# Simple-Fet_-v016-pro-mini.net
KiCad netlist of a schematic drawn in EAGLE
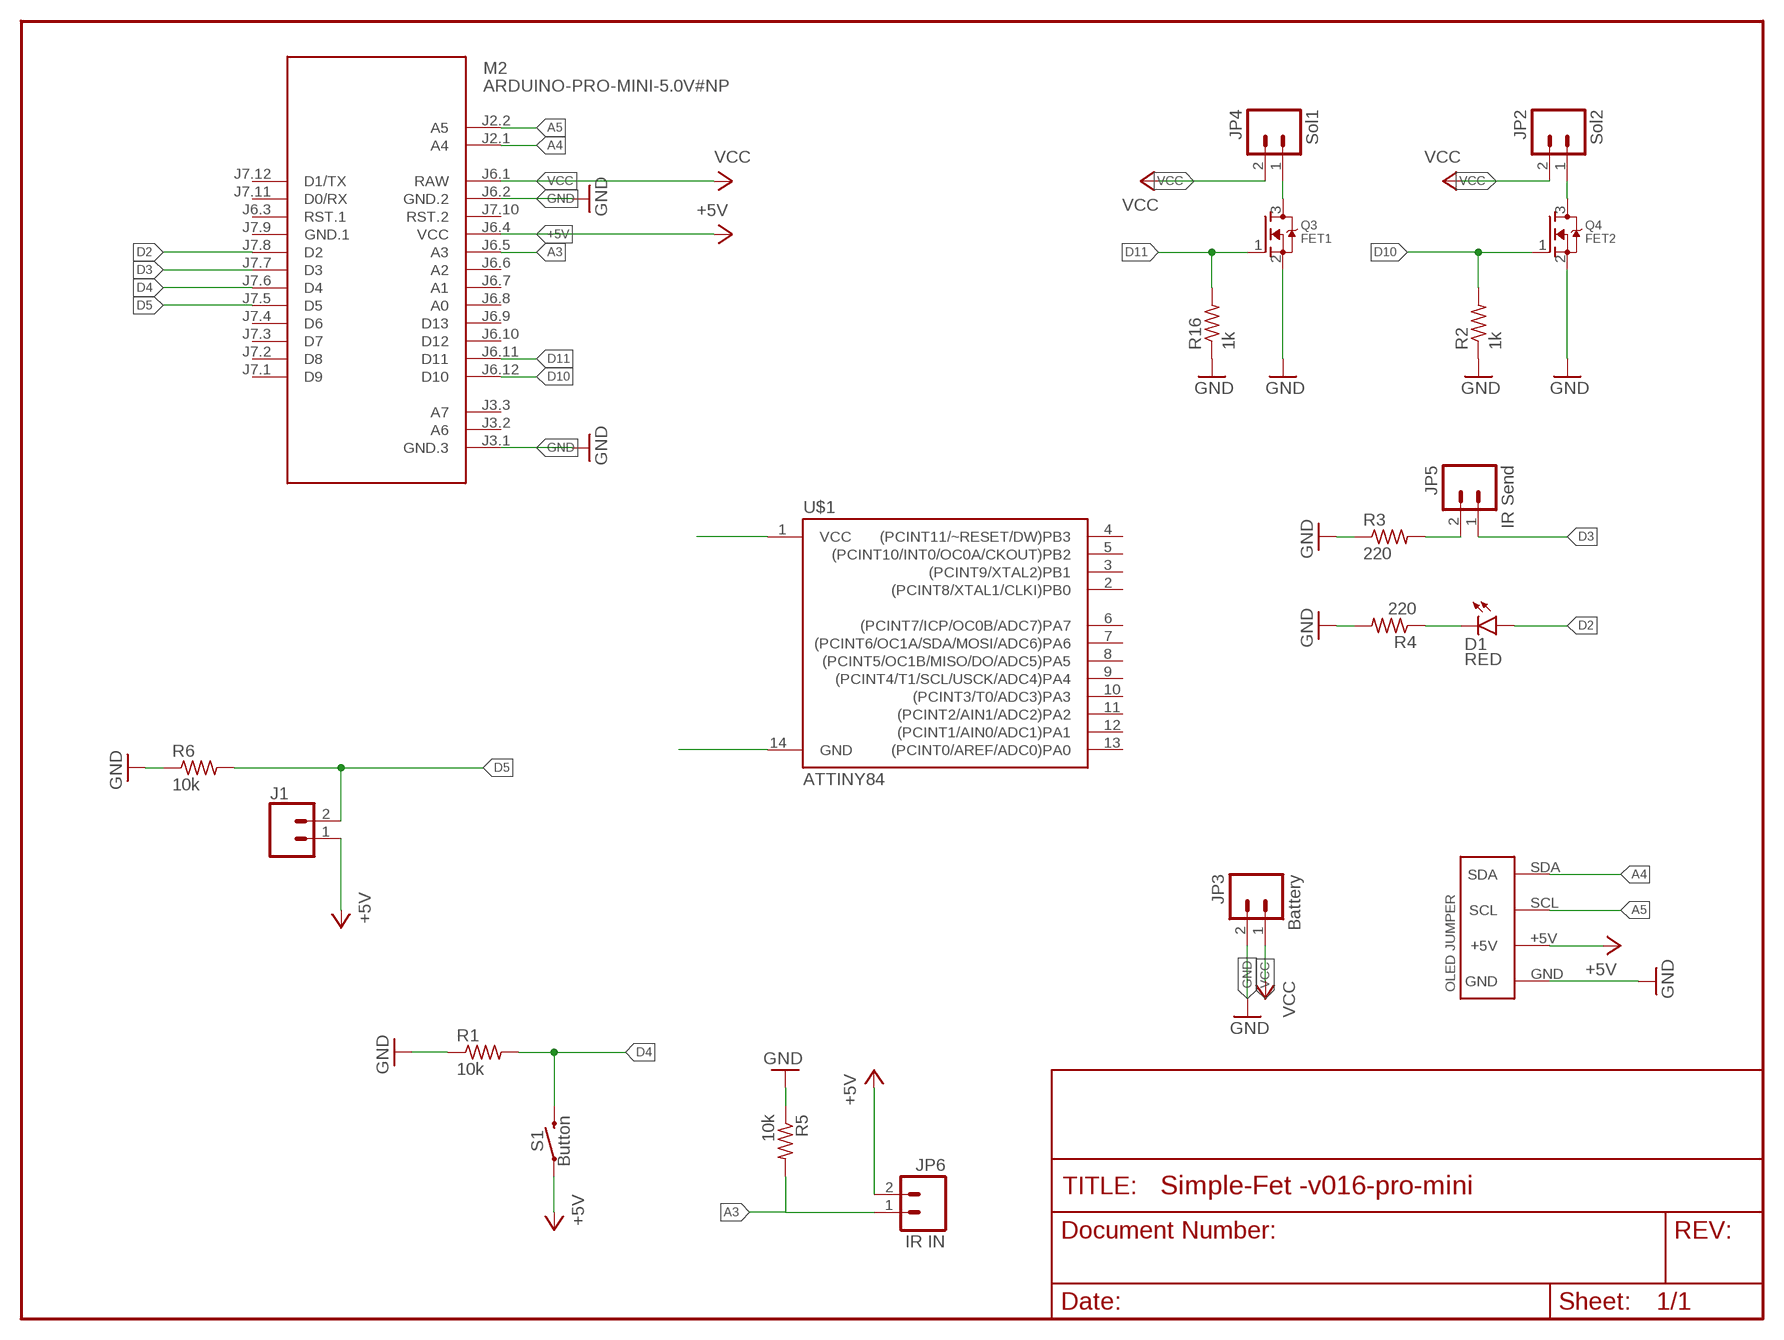
[diagram p0: schematic, sheet 1]

(export (version "E")
  (design (tool "Eeschema 10.0.6"))
  (components
    (comp (ref "D1")
      (value "RED")
      (footprint "eagle-import:LED-1206")
      (fields (field (name "MPN") "HSMC-C150"))
      (libsource (lib "eagle-import") (part "LED-RED1206"))
    )
    (comp (ref "J1")
      (value "CONN_02POGO_PIN_HOLES_ONLY")
      (footprint "eagle-import:1X02_PP_HOLES_ONLY")
      (libsource (lib "eagle-import") (part "CONN_02POGO_PIN_HOLES_ONLY"))
    )
    (comp (ref "JP2")
      (value "Sol2")
      (footprint "eagle-import:1X02")
      (fields (field (name "MF") "MOLEX") (field (name "MPN") "22-23-2021"))
      (libsource (lib "eagle-import") (part "M02PTH"))
    )
    (comp (ref "JP3")
      (value "Battery")
      (footprint "eagle-import:1X02")
      (fields (field (name "MF") "KEYSTONE ELECTR") (field (name "MPN") "2239"))
      (libsource (lib "eagle-import") (part "M02PTH"))
    )
    (comp (ref "JP4")
      (value "Sol1")
      (footprint "eagle-import:1X02")
      (fields (field (name "MF") "MOLEX") (field (name "MPN") "22-23-2021"))
      (libsource (lib "eagle-import") (part "M02PTH"))
    )
    (comp (ref "JP5")
      (value "IR Send")
      (footprint "eagle-import:1X02")
      (fields (field (name "MF") "FAIRCHILD SEMICONDUCTOR") (field (name "MPN") "QEE122"))
      (libsource (lib "eagle-import") (part "M02PTH"))
    )
    (comp (ref "JP6")
      (value "IR IN")
      (footprint "eagle-import:1X02")
      (fields (field (name "MF") "FAIRCHILD SEMICONDUCTOR") (field (name "MPN") "QEE113"))
      (libsource (lib "eagle-import") (part "M02PTH"))
    )
    (comp (ref "M2")
      (value "ARDUINO-PRO-MINI-5.0V#NP")
      (footprint "eagle-import:ARDUINO-PRO-MINI#NP")
      (libsource (lib "eagle-import") (part "ARDUINO-PRO-MINI-#NP5.0V"))
    )
    (comp (ref "Q3")
      (value "FET1")
      (footprint "eagle-import:SOT23")
      (fields (field (name "MPN") "SI2392ADS-T1-GE3"))
      (libsource (lib "eagle-import") (part "MOSFET-NREFLOW"))
    )
    (comp (ref "Q4")
      (value "FET2")
      (footprint "eagle-import:SOT23")
      (fields (field (name "MPN") "SI2392ADS-T1-GE3"))
      (libsource (lib "eagle-import") (part "MOSFET-NREFLOW"))
    )
    (comp (ref "R1")
      (value "10k")
      (footprint "eagle-import:M1206")
      (fields (field (name "MPN") "MC1206S4F1002T5E"))
      (libsource (lib "eagle-import") (part "R-US_M1206"))
    )
    (comp (ref "R2")
      (value "1k")
      (footprint "eagle-import:M1206")
      (fields (field (name "MPN") "RT1206FRE071KL"))
      (libsource (lib "eagle-import") (part "R-US_M1206"))
    )
    (comp (ref "R3")
      (value "220")
      (footprint "eagle-import:M1206")
      (fields (field (name "MF") "BOURNS, INC.") (field (name "MPN") "CR1206FX2200ELF"))
      (libsource (lib "eagle-import") (part "R-US_M1206"))
    )
    (comp (ref "R4")
      (value "220")
      (footprint "eagle-import:M1206")
      (fields (field (name "MF") "BOURNS, INC.") (field (name "MPN") "CR1206FX2200ELF"))
      (libsource (lib "eagle-import") (part "R-US_M1206"))
    )
    (comp (ref "R5")
      (value "10k")
      (footprint "eagle-import:M1206")
      (fields (field (name "MPN") "MC1206S4F1002T5E"))
      (libsource (lib "eagle-import") (part "R-US_M1206"))
    )
    (comp (ref "R6")
      (value "10k")
      (footprint "eagle-import:M1206")
      (fields (field (name "MPN") "MC1206S4F1002T5E"))
      (libsource (lib "eagle-import") (part "R-US_M1206"))
    )
    (comp (ref "R16")
      (value "1k")
      (footprint "eagle-import:M1206")
      (fields (field (name "MPN") "RT1206FRE071KL"))
      (libsource (lib "eagle-import") (part "R-US_M1206"))
    )
    (comp (ref "S1")
      (value "Button")
      (footprint "eagle-import:TACTILE_SWITCH_SMD_6.0X3.5MM")
      (libsource (lib "eagle-import") (part "MOMENTARY-SWITCH-SPST-SMD-6.0X3.5MM"))
    )
    (comp (ref "U$1")
      (value "ATTINY84")
      (footprint "eagle-import:SO14")
      (libsource (lib "eagle-import") (part "ATTINY84"))
    )
    (comp (ref "U$2")
      (value "OLEDHEADER")
      (footprint "eagle-import:OLED-CON")
      (libsource (lib "eagle-import") (part "OLEDHEADER"))
    )
  )
  (nets
    (net (code "1") (name "+5V") (class "Default")
      (node (ref "J1") (pin "1") (pinfunction "1_1") (pintype "passive"))
      (node (ref "JP6") (pin "2") (pinfunction "2_2") (pintype "passive"))
      (node (ref "M2") (pin "J6.4") (pinfunction "VCC_J6.4") (pintype "power_in"))
      (node (ref "S1") (pin "1") (pinfunction "1_1") (pintype "passive"))
      (node (ref "U$2") (pin "+5V") (pinfunction "+5V_+5V") (pintype "bidirectional"))
    )
    (net (code "2") (name "/GND.1") (class "Default")
      (node (ref "M2") (pin "J7.9") (pinfunction "GND.1_J7.9") (pintype "power_in"))
    )
    (net (code "3") (name "A3") (class "Default")
      (node (ref "JP6") (pin "1") (pinfunction "1_1") (pintype "passive"))
      (node (ref "M2") (pin "J6.5") (pinfunction "A3_J6.5") (pintype "bidirectional"))
      (node (ref "R5") (pin "2") (pinfunction "2_2") (pintype "passive"))
    )
    (net (code "4") (name "A4") (class "Default")
      (node (ref "M2") (pin "J2.1") (pinfunction "A4_J2.1") (pintype "bidirectional"))
      (node (ref "U$2") (pin "SDA") (pinfunction "SDA_SDA") (pintype "bidirectional"))
    )
    (net (code "5") (name "A5") (class "Default")
      (node (ref "M2") (pin "J2.2") (pinfunction "A5_J2.2") (pintype "bidirectional"))
      (node (ref "U$2") (pin "SCL") (pinfunction "SCL_SCL") (pintype "bidirectional"))
    )
    (net (code "6") (name "D2") (class "Default")
      (node (ref "D1") (pin "A") (pinfunction "A_A") (pintype "passive"))
      (node (ref "M2") (pin "J7.8") (pinfunction "D2_J7.8") (pintype "bidirectional"))
    )
    (net (code "7") (name "D3") (class "Default")
      (node (ref "JP5") (pin "1") (pinfunction "1_1") (pintype "passive"))
      (node (ref "M2") (pin "J7.7") (pinfunction "D3_J7.7") (pintype "bidirectional"))
    )
    (net (code "8") (name "D4") (class "Default")
      (node (ref "M2") (pin "J7.6") (pinfunction "D4_J7.6") (pintype "bidirectional"))
      (node (ref "R1") (pin "2") (pinfunction "2_2") (pintype "passive"))
      (node (ref "S1") (pin "2") (pinfunction "2_2") (pintype "passive"))
    )
    (net (code "9") (name "D5") (class "Default")
      (node (ref "J1") (pin "2") (pinfunction "2_2") (pintype "passive"))
      (node (ref "M2") (pin "J7.5") (pinfunction "D5_J7.5") (pintype "bidirectional"))
      (node (ref "R6") (pin "2") (pinfunction "2_2") (pintype "passive"))
    )
    (net (code "10") (name "D10") (class "Default")
      (node (ref "M2") (pin "J6.12") (pinfunction "D10_J6.12") (pintype "bidirectional"))
      (node (ref "Q4") (pin "1") (pinfunction "G_1") (pintype "bidirectional"))
      (node (ref "R2") (pin "2") (pinfunction "2_2") (pintype "passive"))
    )
    (net (code "11") (name "D11") (class "Default")
      (node (ref "M2") (pin "J6.11") (pinfunction "D11_J6.11") (pintype "bidirectional"))
      (node (ref "Q3") (pin "1") (pinfunction "G_1") (pintype "bidirectional"))
      (node (ref "R16") (pin "2") (pinfunction "2_2") (pintype "passive"))
    )
    (net (code "12") (name "GND") (class "Default")
      (node (ref "JP3") (pin "2") (pinfunction "2_2") (pintype "passive"))
      (node (ref "M2") (pin "J3.1") (pinfunction "GND.3_J3.1") (pintype "bidirectional"))
      (node (ref "M2") (pin "J6.2") (pinfunction "GND.2_J6.2") (pintype "power_in"))
      (node (ref "Q3") (pin "2") (pinfunction "S_2") (pintype "bidirectional"))
      (node (ref "Q4") (pin "2") (pinfunction "S_2") (pintype "bidirectional"))
      (node (ref "R1") (pin "1") (pinfunction "1_1") (pintype "passive"))
      (node (ref "R16") (pin "1") (pinfunction "1_1") (pintype "passive"))
      (node (ref "R2") (pin "1") (pinfunction "1_1") (pintype "passive"))
      (node (ref "R3") (pin "1") (pinfunction "1_1") (pintype "passive"))
      (node (ref "R4") (pin "2") (pinfunction "2_2") (pintype "passive"))
      (node (ref "R5") (pin "1") (pinfunction "1_1") (pintype "passive"))
      (node (ref "R6") (pin "1") (pinfunction "1_1") (pintype "passive"))
      (node (ref "U$2") (pin "GND") (pinfunction "GND_GND") (pintype "bidirectional"))
    )
    (net (code "13") (name "Net-(D1-PadC)") (class "Default")
      (node (ref "D1") (pin "C") (pinfunction "C_C") (pintype "passive"))
      (node (ref "R4") (pin "1") (pinfunction "1_1") (pintype "passive"))
    )
    (net (code "14") (name "Net-(JP5-Pad2)") (class "Default")
      (node (ref "JP5") (pin "2") (pinfunction "2_2") (pintype "passive"))
      (node (ref "R3") (pin "2") (pinfunction "2_2") (pintype "passive"))
    )
    (net (code "15") (name "Net-(Q3-D)") (class "Default")
      (node (ref "JP4") (pin "1") (pinfunction "1_1") (pintype "passive"))
      (node (ref "Q3") (pin "3") (pinfunction "D_3") (pintype "bidirectional"))
    )
    (net (code "16") (name "Net-(Q4-D)") (class "Default")
      (node (ref "JP2") (pin "1") (pinfunction "1_1") (pintype "passive"))
      (node (ref "Q4") (pin "3") (pinfunction "D_3") (pintype "bidirectional"))
    )
    (net (code "17") (name "VCC") (class "Default")
      (node (ref "JP2") (pin "2") (pinfunction "2_2") (pintype "passive"))
      (node (ref "JP3") (pin "1") (pinfunction "1_1") (pintype "passive"))
      (node (ref "JP4") (pin "2") (pinfunction "2_2") (pintype "passive"))
      (node (ref "M2") (pin "J6.1") (pinfunction "RAW_J6.1") (pintype "power_in"))
    )
    (net (code "18") (name "unconnected-(M2-A0-PadJ6.8)") (class "Default")
      (node (ref "M2") (pin "J6.8") (pinfunction "A0_J6.8") (pintype "bidirectional"))
    )
    (net (code "19") (name "unconnected-(M2-A1-PadJ6.7)") (class "Default")
      (node (ref "M2") (pin "J6.7") (pinfunction "A1_J6.7") (pintype "bidirectional"))
    )
    (net (code "20") (name "unconnected-(M2-A2-PadJ6.6)") (class "Default")
      (node (ref "M2") (pin "J6.6") (pinfunction "A2_J6.6") (pintype "bidirectional"))
    )
    (net (code "21") (name "unconnected-(M2-A6-PadJ3.2)") (class "Default")
      (node (ref "M2") (pin "J3.2") (pinfunction "A6_J3.2") (pintype "bidirectional"))
    )
    (net (code "22") (name "unconnected-(M2-A7-PadJ3.3)") (class "Default")
      (node (ref "M2") (pin "J3.3") (pinfunction "A7_J3.3") (pintype "bidirectional"))
    )
    (net (code "23") (name "unconnected-(M2-D0{slash}RX-PadJ7.11)") (class "Default")
      (node (ref "M2") (pin "J7.11") (pinfunction "D0/RX_J7.11") (pintype "bidirectional"))
    )
    (net (code "24") (name "unconnected-(M2-D1{slash}TX-PadJ7.12)") (class "Default")
      (node (ref "M2") (pin "J7.12") (pinfunction "D1/TX_J7.12") (pintype "bidirectional"))
    )
    (net (code "25") (name "unconnected-(M2-D6-PadJ7.4)") (class "Default")
      (node (ref "M2") (pin "J7.4") (pinfunction "D6_J7.4") (pintype "bidirectional"))
    )
    (net (code "26") (name "unconnected-(M2-D7-PadJ7.3)") (class "Default")
      (node (ref "M2") (pin "J7.3") (pinfunction "D7_J7.3") (pintype "bidirectional"))
    )
    (net (code "27") (name "unconnected-(M2-D8-PadJ7.2)") (class "Default")
      (node (ref "M2") (pin "J7.2") (pinfunction "D8_J7.2") (pintype "bidirectional"))
    )
    (net (code "28") (name "unconnected-(M2-D9-PadJ7.1)") (class "Default")
      (node (ref "M2") (pin "J7.1") (pinfunction "D9_J7.1") (pintype "bidirectional"))
    )
    (net (code "29") (name "unconnected-(M2-D12-PadJ6.10)") (class "Default")
      (node (ref "M2") (pin "J6.10") (pinfunction "D12_J6.10") (pintype "bidirectional"))
    )
    (net (code "30") (name "unconnected-(M2-D13-PadJ6.9)") (class "Default")
      (node (ref "M2") (pin "J6.9") (pinfunction "D13_J6.9") (pintype "bidirectional"))
    )
    (net (code "31") (name "unconnected-(M2-RST.1-PadJ6.3)") (class "Default")
      (node (ref "M2") (pin "J6.3") (pinfunction "RST.1_J6.3") (pintype "bidirectional"))
    )
    (net (code "32") (name "unconnected-(M2-RST.2-PadJ7.10)") (class "Default")
      (node (ref "M2") (pin "J7.10") (pinfunction "RST.2_J7.10") (pintype "bidirectional"))
    )
    (net (code "33") (name "unconnected-(U$1-(PCINT0{slash}AREF{slash}ADC0)PA0-Pad13)") (class "Default")
      (node (ref "U$1") (pin "13") (pinfunction "(PCINT0/AREF/ADC0)PA0_13") (pintype "bidirectional"))
    )
    (net (code "34") (name "unconnected-(U$1-(PCINT1{slash}AIN0{slash}ADC1)PA1-Pad12)") (class "Default")
      (node (ref "U$1") (pin "12") (pinfunction "(PCINT1/AIN0/ADC1)PA1_12") (pintype "bidirectional"))
    )
    (net (code "35") (name "unconnected-(U$1-(PCINT2{slash}AIN1{slash}ADC2)PA2-Pad11)") (class "Default")
      (node (ref "U$1") (pin "11") (pinfunction "(PCINT2/AIN1/ADC2)PA2_11") (pintype "bidirectional"))
    )
    (net (code "36") (name "unconnected-(U$1-(PCINT3{slash}T0{slash}ADC3)PA3-Pad10)") (class "Default")
      (node (ref "U$1") (pin "10") (pinfunction "(PCINT3/T0/ADC3)PA3_10") (pintype "bidirectional"))
    )
    (net (code "37") (name "unconnected-(U$1-(PCINT4{slash}T1{slash}SCL{slash}USCK{slash}ADC4)PA4-Pad9)") (class "Default")
      (node (ref "U$1") (pin "9") (pinfunction "(PCINT4/T1/SCL/USCK/ADC4)PA4_9") (pintype "bidirectional"))
    )
    (net (code "38") (name "unconnected-(U$1-(PCINT5{slash}OC1B{slash}MISO{slash}DO{slash}ADC5)PA5-Pad8)") (class "Default")
      (node (ref "U$1") (pin "8") (pinfunction "(PCINT5/OC1B/MISO/DO/ADC5)PA5_8") (pintype "bidirectional"))
    )
    (net (code "39") (name "unconnected-(U$1-(PCINT6{slash}OC1A{slash}SDA{slash}MOSI{slash}ADC6)PA6-Pad7)") (class "Default")
      (node (ref "U$1") (pin "7") (pinfunction "(PCINT6/OC1A/SDA/MOSI/ADC6)PA6_7") (pintype "bidirectional"))
    )
    (net (code "40") (name "unconnected-(U$1-(PCINT7{slash}ICP{slash}OC0B{slash}ADC7)PA7-Pad6)") (class "Default")
      (node (ref "U$1") (pin "6") (pinfunction "(PCINT7/ICP/OC0B/ADC7)PA7_6") (pintype "bidirectional"))
    )
    (net (code "41") (name "unconnected-(U$1-(PCINT8{slash}XTAL1{slash}CLKI)PB0-Pad2)") (class "Default")
      (node (ref "U$1") (pin "2") (pinfunction "(PCINT8/XTAL1/CLKI)PB0_2") (pintype "bidirectional"))
    )
    (net (code "42") (name "unconnected-(U$1-(PCINT9{slash}XTAL2)PB1-Pad3)") (class "Default")
      (node (ref "U$1") (pin "3") (pinfunction "(PCINT9/XTAL2)PB1_3") (pintype "bidirectional"))
    )
    (net (code "43") (name "unconnected-(U$1-(PCINT10{slash}INT0{slash}OC0A{slash}CKOUT)PB2-Pad5)") (class "Default")
      (node (ref "U$1") (pin "5") (pinfunction "(PCINT10/INT0/OC0A/CKOUT)PB2_5") (pintype "bidirectional"))
    )
    (net (code "44") (name "unconnected-(U$1-(PCINT11{slash}~{RESET{slash}DW})PB3-Pad4)") (class "Default")
      (node (ref "U$1") (pin "4") (pinfunction "(PCINT11/~{RESET/DW})PB3_4") (pintype "bidirectional"))
    )
    (net (code "45") (name "unconnected-(U$1-GND-Pad14)") (class "Default")
      (node (ref "U$1") (pin "14") (pinfunction "GND_14") (pintype "bidirectional"))
    )
    (net (code "46") (name "unconnected-(U$1-VCC-Pad1)") (class "Default")
      (node (ref "U$1") (pin "1") (pinfunction "VCC_1") (pintype "bidirectional"))
    )
  )
)
